# blinder.net
KiCad netlist of a schematic drawn in EAGLE
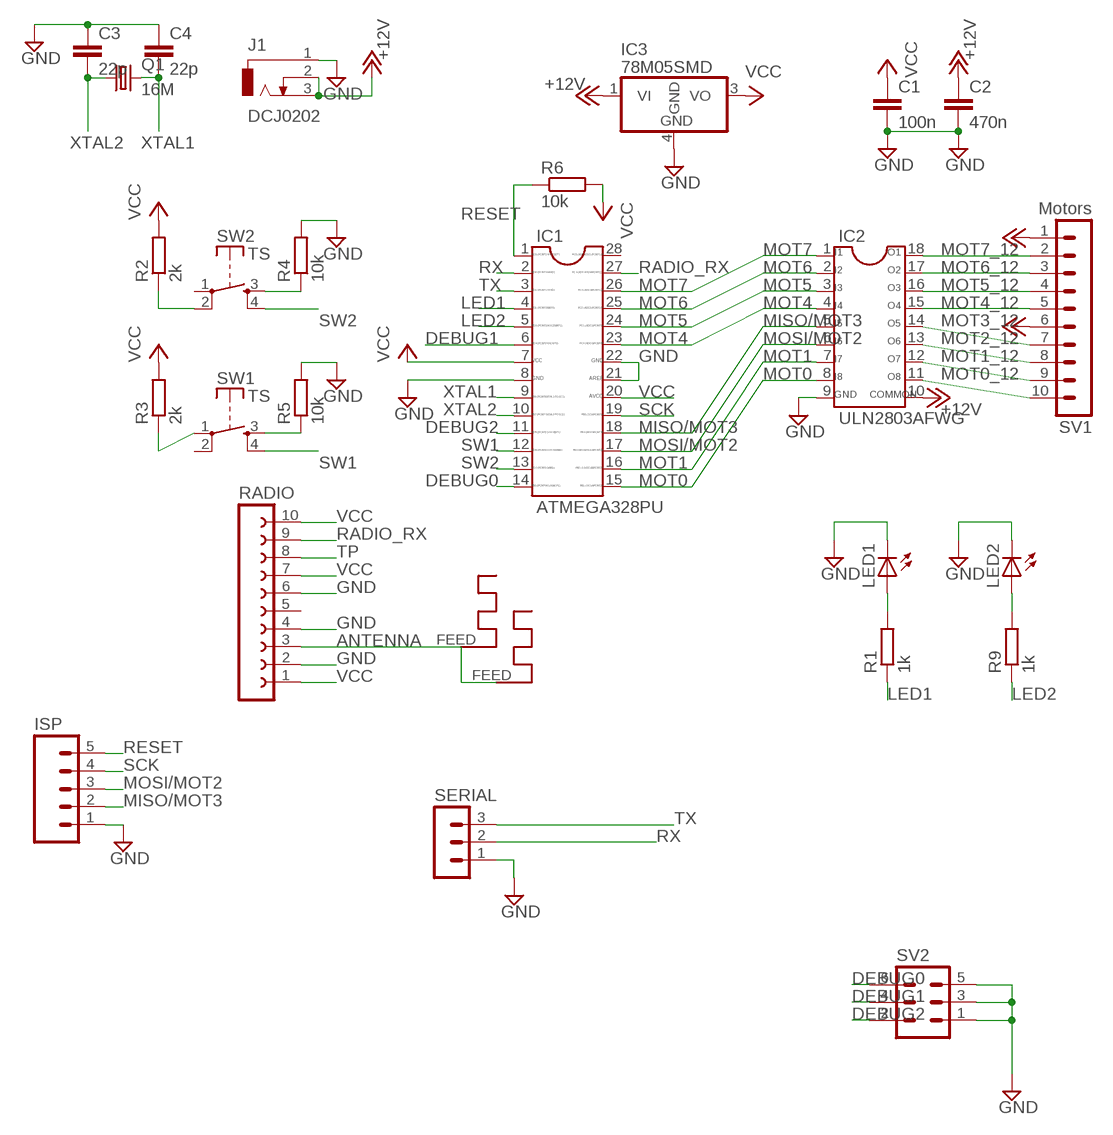
[diagram p0: schematic, sheet 1]

(export (version "E")
  (design (tool "Eeschema 10.0.6"))
  (components
    (comp (ref "C1")
      (value "100n")
      (footprint "eagle-import:C0805")
      (libsource (lib "eagle-import") (part "C-EUC0805"))
    )
    (comp (ref "C2")
      (value "470n")
      (footprint "eagle-import:C0805")
      (libsource (lib "eagle-import") (part "C-EUC0805"))
    )
    (comp (ref "C3")
      (value "22p")
      (footprint "eagle-import:C0805")
      (libsource (lib "eagle-import") (part "C-EUC0805"))
    )
    (comp (ref "C4")
      (value "22p")
      (footprint "eagle-import:C0805")
      (libsource (lib "eagle-import") (part "C-EUC0805"))
    )
    (comp (ref "IC1")
      (value "ATMEGA328PU")
      (footprint "eagle-import:DIL28-3")
      (libsource (lib "eagle-import") (part "ATMEGA328P-3"))
    )
    (comp (ref "IC2")
      (value "ULN2803AFWG")
      (footprint "eagle-import:DIL18")
      (libsource (lib "eagle-import") (part "ULN2803AFWG"))
    )
    (comp (ref "IC3")
      (value "78M05SMD")
      (footprint "eagle-import:DPACK")
      (libsource (lib "eagle-import") (part "78M05SMD"))
    )
    (comp (ref "ISP")
      (value "M05LOCK")
      (footprint "eagle-import:1X05_LOCK")
      (libsource (lib "eagle-import") (part "M05LOCK"))
    )
    (comp (ref "J1")
      (value "DCJ0202")
      (footprint "eagle-import:DCJ0202")
      (libsource (lib "eagle-import") (part "DCJ0202"))
    )
    (comp (ref "LED1")
      (value "LED3MM")
      (footprint "eagle-import:LED3MM")
      (libsource (lib "eagle-import") (part "LED3MM"))
    )
    (comp (ref "LED2")
      (value "LED3MM")
      (footprint "eagle-import:LED3MM")
      (libsource (lib "eagle-import") (part "LED3MM"))
    )
    (comp (ref "Q1")
      (value "16M")
      (footprint "eagle-import:HC18U-V")
      (libsource (lib "eagle-import") (part "CRYSTALHC18U-V"))
    )
    (comp (ref "R1")
      (value "1k")
      (footprint "eagle-import:R0805")
      (libsource (lib "eagle-import") (part "R-EU_R0805"))
    )
    (comp (ref "R2")
      (value "2k")
      (footprint "eagle-import:R0805")
      (libsource (lib "eagle-import") (part "R-EU_R0805"))
    )
    (comp (ref "R3")
      (value "2k")
      (footprint "eagle-import:R0805")
      (libsource (lib "eagle-import") (part "R-EU_R0805"))
    )
    (comp (ref "R4")
      (value "10k")
      (footprint "eagle-import:R0805")
      (libsource (lib "eagle-import") (part "R-EU_R0805"))
    )
    (comp (ref "R5")
      (value "10k")
      (footprint "eagle-import:R0805")
      (libsource (lib "eagle-import") (part "R-EU_R0805"))
    )
    (comp (ref "R6")
      (value "10k")
      (footprint "eagle-import:R0805")
      (libsource (lib "eagle-import") (part "R-EU_R0805"))
    )
    (comp (ref "R9")
      (value "1k")
      (footprint "eagle-import:R0805")
      (libsource (lib "eagle-import") (part "R-EU_R0805"))
    )
    (comp (ref "RADIO")
      (value "FE10W")
      (footprint "eagle-import:FE10W")
      (libsource (lib "eagle-import") (part "FE10W"))
    )
    (comp (ref "SERIAL")
      (value "MA03-1")
      (footprint "eagle-import:MA03-1")
      (fields (field (name "OC_FARNELL") "unknown") (field (name "OC_NEWARK") "unknown"))
      (libsource (lib "eagle-import") (part "MA03-1"))
    )
    (comp (ref "SV1")
      (value "Motors")
      (footprint "eagle-import:MA10-1W")
      (libsource (lib "eagle-import") (part "MA10-1W"))
    )
    (comp (ref "SV2")
      (value "MA03-2")
      (footprint "eagle-import:MA03-2")
      (libsource (lib "eagle-import") (part "MA03-2"))
    )
    (comp (ref "SW1") (value "TS") (footprint "eagle-import:TS") (libsource (lib "eagle-import") (part "TS")))
    (comp (ref "SW2") (value "TS") (footprint "eagle-import:TS") (libsource (lib "eagle-import") (part "TS")))
    (comp (ref "U$1")
      (value "ANT44350H")
      (footprint "eagle-import:DIPOLEHALF443.95_50")
      (libsource (lib "eagle-import") (part "ANT44350H"))
    )
    (comp (ref "U$2")
      (value "ANT44350H")
      (footprint "eagle-import:DIPOLEHALF443.95_50")
      (libsource (lib "eagle-import") (part "ANT44350H"))
    )
  )
  (nets
    (net (code "1") (name "+12V") (class "Default")
      (node (ref "C2") (pin "1") (pinfunction "1_1") (pintype "passive"))
      (node (ref "IC2") (pin "10") (pinfunction "COMMON_10") (pintype "passive"))
      (node (ref "IC3") (pin "1") (pinfunction "VI_1") (pintype "input"))
      (node (ref "J1") (pin "2") (pinfunction "2_2") (pintype "passive"))
      (node (ref "J1") (pin "3") (pinfunction "3_3") (pintype "passive"))
      (node (ref "SV1") (pin "1") (pinfunction "1_1") (pintype "passive"))
      (node (ref "SV1") (pin "6") (pinfunction "6_6") (pintype "passive"))
    )
    (net (code "2") (name "/ANTENNA") (class "Default")
      (node (ref "RADIO") (pin "3") (pinfunction "3_3") (pintype "passive"))
      (node (ref "U$1") (pin "FEED") (pinfunction "FEED_FEED") (pintype "passive"))
      (node (ref "U$2") (pin "FEED") (pinfunction "FEED_FEED") (pintype "passive"))
    )
    (net (code "3") (name "/DEBUG0") (class "Default")
      (node (ref "IC1") (pin "14") (pinfunction "PB0_14") (pintype "passive"))
      (node (ref "SV2") (pin "6") (pinfunction "6_6") (pintype "passive"))
    )
    (net (code "4") (name "/DEBUG1") (class "Default")
      (node (ref "IC1") (pin "6") (pinfunction "PD4_6") (pintype "passive"))
      (node (ref "SV2") (pin "4") (pinfunction "4_4") (pintype "passive"))
    )
    (net (code "5") (name "/DEBUG2") (class "Default")
      (node (ref "IC1") (pin "11") (pinfunction "PD5_11") (pintype "passive"))
      (node (ref "SV2") (pin "2") (pinfunction "2_2") (pintype "passive"))
    )
    (net (code "6") (name "/LED1") (class "Default")
      (node (ref "IC1") (pin "4") (pinfunction "PD2_4") (pintype "passive"))
      (node (ref "R1") (pin "1") (pinfunction "1_1") (pintype "passive"))
    )
    (net (code "7") (name "/LED2") (class "Default")
      (node (ref "IC1") (pin "5") (pinfunction "PD3_5") (pintype "passive"))
      (node (ref "R9") (pin "1") (pinfunction "1_1") (pintype "passive"))
    )
    (net (code "8") (name "/MISO{slash}MOT3") (class "Default")
      (node (ref "IC1") (pin "18") (pinfunction "PB4_18") (pintype "passive"))
      (node (ref "IC2") (pin "5") (pinfunction "I5_5") (pintype "passive"))
      (node (ref "ISP") (pin "2") (pinfunction "2_2") (pintype "passive"))
    )
    (net (code "9") (name "/MOSI{slash}MOT2") (class "Default")
      (node (ref "IC1") (pin "17") (pinfunction "PB3_17") (pintype "passive"))
      (node (ref "IC2") (pin "6") (pinfunction "I6_6") (pintype "passive"))
      (node (ref "ISP") (pin "3") (pinfunction "3_3") (pintype "passive"))
    )
    (net (code "10") (name "/MOT0") (class "Default")
      (node (ref "IC1") (pin "15") (pinfunction "PB1_15") (pintype "passive"))
      (node (ref "IC2") (pin "8") (pinfunction "I8_8") (pintype "passive"))
    )
    (net (code "11") (name "/MOT0_12") (class "Default")
      (node (ref "IC2") (pin "11") (pinfunction "O8_11") (pintype "passive"))
      (node (ref "SV1") (pin "10") (pinfunction "10_10") (pintype "passive"))
    )
    (net (code "12") (name "/MOT1") (class "Default")
      (node (ref "IC1") (pin "16") (pinfunction "PB2_16") (pintype "passive"))
      (node (ref "IC2") (pin "7") (pinfunction "I7_7") (pintype "passive"))
    )
    (net (code "13") (name "/MOT1_12") (class "Default")
      (node (ref "IC2") (pin "12") (pinfunction "O7_12") (pintype "passive"))
      (node (ref "SV1") (pin "9") (pinfunction "9_9") (pintype "passive"))
    )
    (net (code "14") (name "/MOT2_12") (class "Default")
      (node (ref "IC2") (pin "13") (pinfunction "O6_13") (pintype "passive"))
      (node (ref "SV1") (pin "8") (pinfunction "8_8") (pintype "passive"))
    )
    (net (code "15") (name "/MOT3_12") (class "Default")
      (node (ref "IC2") (pin "14") (pinfunction "O5_14") (pintype "passive"))
      (node (ref "SV1") (pin "7") (pinfunction "7_7") (pintype "passive"))
    )
    (net (code "16") (name "/MOT4") (class "Default")
      (node (ref "IC1") (pin "23") (pinfunction "PC0_23") (pintype "passive"))
      (node (ref "IC2") (pin "4") (pinfunction "I4_4") (pintype "passive"))
    )
    (net (code "17") (name "/MOT4_12") (class "Default")
      (node (ref "IC2") (pin "15") (pinfunction "O4_15") (pintype "passive"))
      (node (ref "SV1") (pin "5") (pinfunction "5_5") (pintype "passive"))
    )
    (net (code "18") (name "/MOT5") (class "Default")
      (node (ref "IC1") (pin "24") (pinfunction "PC1_24") (pintype "passive"))
      (node (ref "IC2") (pin "3") (pinfunction "I3_3") (pintype "passive"))
    )
    (net (code "19") (name "/MOT5_12") (class "Default")
      (node (ref "IC2") (pin "16") (pinfunction "O3_16") (pintype "passive"))
      (node (ref "SV1") (pin "4") (pinfunction "4_4") (pintype "passive"))
    )
    (net (code "20") (name "/MOT6") (class "Default")
      (node (ref "IC1") (pin "25") (pinfunction "PC2_25") (pintype "passive"))
      (node (ref "IC2") (pin "2") (pinfunction "I2_2") (pintype "passive"))
    )
    (net (code "21") (name "/MOT6_12") (class "Default")
      (node (ref "IC2") (pin "17") (pinfunction "O2_17") (pintype "passive"))
      (node (ref "SV1") (pin "3") (pinfunction "3_3") (pintype "passive"))
    )
    (net (code "22") (name "/MOT7") (class "Default")
      (node (ref "IC1") (pin "26") (pinfunction "PC3_26") (pintype "passive"))
      (node (ref "IC2") (pin "1") (pinfunction "I1_1") (pintype "passive"))
    )
    (net (code "23") (name "/MOT7_12") (class "Default")
      (node (ref "IC2") (pin "18") (pinfunction "O1_18") (pintype "passive"))
      (node (ref "SV1") (pin "2") (pinfunction "2_2") (pintype "passive"))
    )
    (net (code "24") (name "/RADIO_RX") (class "Default")
      (node (ref "IC1") (pin "27") (pinfunction "PC4_27") (pintype "passive"))
      (node (ref "RADIO") (pin "9") (pinfunction "9_9") (pintype "passive"))
    )
    (net (code "25") (name "/RESET") (class "Default")
      (node (ref "IC1") (pin "1") (pinfunction "PC6_1") (pintype "passive"))
      (node (ref "ISP") (pin "5") (pinfunction "5_5") (pintype "passive"))
      (node (ref "R6") (pin "1") (pinfunction "1_1") (pintype "passive"))
    )
    (net (code "26") (name "/RX") (class "Default")
      (node (ref "IC1") (pin "2") (pinfunction "PD0_2") (pintype "passive"))
      (node (ref "SERIAL") (pin "2") (pinfunction "2_2") (pintype "passive"))
    )
    (net (code "27") (name "/SCK") (class "Default")
      (node (ref "IC1") (pin "19") (pinfunction "PB5_19") (pintype "passive"))
      (node (ref "ISP") (pin "4") (pinfunction "4_4") (pintype "passive"))
    )
    (net (code "28") (name "/SW1") (class "Default")
      (node (ref "IC1") (pin "12") (pinfunction "PD6_12") (pintype "passive"))
      (node (ref "SW1") (pin "4") (pinfunction "S_4") (pintype "passive"))
    )
    (net (code "29") (name "/SW2") (class "Default")
      (node (ref "IC1") (pin "13") (pinfunction "PD7_13") (pintype "passive"))
      (node (ref "SW2") (pin "4") (pinfunction "S_4") (pintype "passive"))
    )
    (net (code "30") (name "/TP") (class "Default")
      (node (ref "RADIO") (pin "8") (pinfunction "8_8") (pintype "passive"))
    )
    (net (code "31") (name "/TX") (class "Default")
      (node (ref "IC1") (pin "3") (pinfunction "PD1_3") (pintype "passive"))
      (node (ref "SERIAL") (pin "3") (pinfunction "3_3") (pintype "passive"))
    )
    (net (code "32") (name "/XTAL1") (class "Default")
      (node (ref "C4") (pin "2") (pinfunction "2_2") (pintype "passive"))
      (node (ref "IC1") (pin "9") (pinfunction "PB6_9") (pintype "passive"))
      (node (ref "Q1") (pin "2") (pinfunction "2_2") (pintype "passive"))
    )
    (net (code "33") (name "/XTAL2") (class "Default")
      (node (ref "C3") (pin "2") (pinfunction "2_2") (pintype "passive"))
      (node (ref "IC1") (pin "10") (pinfunction "PB7_10") (pintype "passive"))
      (node (ref "Q1") (pin "1") (pinfunction "1_1") (pintype "passive"))
    )
    (net (code "34") (name "GND") (class "Default")
      (node (ref "C1") (pin "2") (pinfunction "2_2") (pintype "passive"))
      (node (ref "C2") (pin "2") (pinfunction "2_2") (pintype "passive"))
      (node (ref "C3") (pin "1") (pinfunction "1_1") (pintype "passive"))
      (node (ref "C4") (pin "1") (pinfunction "1_1") (pintype "passive"))
      (node (ref "IC1") (pin "21") (pinfunction "AREF_21") (pintype "passive"))
      (node (ref "IC1") (pin "22") (pinfunction "GND2_22") (pintype "passive"))
      (node (ref "IC1") (pin "8") (pinfunction "GND_8") (pintype "passive"))
      (node (ref "IC2") (pin "9") (pinfunction "GND_9") (pintype "passive"))
      (node (ref "IC3") (pin "4") (pinfunction "GND_4") (pintype "passive"))
      (node (ref "ISP") (pin "1") (pinfunction "1_1") (pintype "passive"))
      (node (ref "J1") (pin "1") (pinfunction "1_1") (pintype "passive"))
      (node (ref "LED1") (pin "K") (pinfunction "C_K") (pintype "passive"))
      (node (ref "LED2") (pin "K") (pinfunction "C_K") (pintype "passive"))
      (node (ref "R4") (pin "2") (pinfunction "2_2") (pintype "passive"))
      (node (ref "R5") (pin "2") (pinfunction "2_2") (pintype "passive"))
      (node (ref "RADIO") (pin "2") (pinfunction "2_2") (pintype "passive"))
      (node (ref "RADIO") (pin "4") (pinfunction "4_4") (pintype "passive"))
      (node (ref "RADIO") (pin "6") (pinfunction "6_6") (pintype "passive"))
      (node (ref "SERIAL") (pin "1") (pinfunction "1_1") (pintype "passive"))
      (node (ref "SV2") (pin "1") (pinfunction "1_1") (pintype "passive"))
      (node (ref "SV2") (pin "3") (pinfunction "3_3") (pintype "passive"))
      (node (ref "SV2") (pin "5") (pinfunction "5_5") (pintype "passive"))
    )
    (net (code "35") (name "Net-(LED1-PadA)") (class "Default")
      (node (ref "LED1") (pin "A") (pinfunction "A_A") (pintype "passive"))
      (node (ref "R1") (pin "2") (pinfunction "2_2") (pintype "passive"))
    )
    (net (code "36") (name "Net-(LED2-PadA)") (class "Default")
      (node (ref "LED2") (pin "A") (pinfunction "A_A") (pintype "passive"))
      (node (ref "R9") (pin "2") (pinfunction "2_2") (pintype "passive"))
    )
    (net (code "37") (name "Net-(R2-Pad1)") (class "Default")
      (node (ref "R2") (pin "1") (pinfunction "1_1") (pintype "passive"))
      (node (ref "SW2") (pin "2") (pinfunction "P_2") (pintype "passive"))
    )
    (net (code "38") (name "Net-(R3-Pad1)") (class "Default")
      (node (ref "R3") (pin "1") (pinfunction "1_1") (pintype "passive"))
      (node (ref "SW1") (pin "1") (pinfunction "P_1") (pintype "passive"))
    )
    (net (code "39") (name "Net-(R4-Pad1)") (class "Default")
      (node (ref "R4") (pin "1") (pinfunction "1_1") (pintype "passive"))
      (node (ref "SW2") (pin "3") (pinfunction "S_3") (pintype "passive"))
    )
    (net (code "40") (name "Net-(R5-Pad1)") (class "Default")
      (node (ref "R5") (pin "1") (pinfunction "1_1") (pintype "passive"))
      (node (ref "SW1") (pin "3") (pinfunction "S_3") (pintype "passive"))
    )
    (net (code "41") (name "VCC") (class "Default")
      (node (ref "C1") (pin "1") (pinfunction "1_1") (pintype "passive"))
      (node (ref "IC1") (pin "20") (pinfunction "AVCC_20") (pintype "passive"))
      (node (ref "IC1") (pin "7") (pinfunction "VCC_7") (pintype "passive"))
      (node (ref "IC3") (pin "3") (pinfunction "VO_3") (pintype "passive"))
      (node (ref "R2") (pin "2") (pinfunction "2_2") (pintype "passive"))
      (node (ref "R3") (pin "2") (pinfunction "2_2") (pintype "passive"))
      (node (ref "R6") (pin "2") (pinfunction "2_2") (pintype "passive"))
      (node (ref "RADIO") (pin "1") (pinfunction "1_1") (pintype "passive"))
      (node (ref "RADIO") (pin "10") (pinfunction "10_10") (pintype "passive"))
      (node (ref "RADIO") (pin "7") (pinfunction "7_7") (pintype "passive"))
    )
    (net (code "42") (name "unconnected-(IC1-PC5-Pad28)") (class "Default")
      (node (ref "IC1") (pin "28") (pinfunction "PC5_28") (pintype "passive"))
    )
    (net (code "43") (name "unconnected-(RADIO-Pad5)") (class "Default")
      (node (ref "RADIO") (pin "5") (pinfunction "5_5") (pintype "passive"))
    )
    (net (code "44") (name "unconnected-(SW1-P-Pad2)") (class "Default")
      (node (ref "SW1") (pin "2") (pinfunction "P_2") (pintype "passive"))
    )
    (net (code "45") (name "unconnected-(SW2-P-Pad1)") (class "Default")
      (node (ref "SW2") (pin "1") (pinfunction "P_1") (pintype "passive"))
    )
  )
)
